# 6_LIN.net
KiCad netlist of a schematic drawn in EAGLE
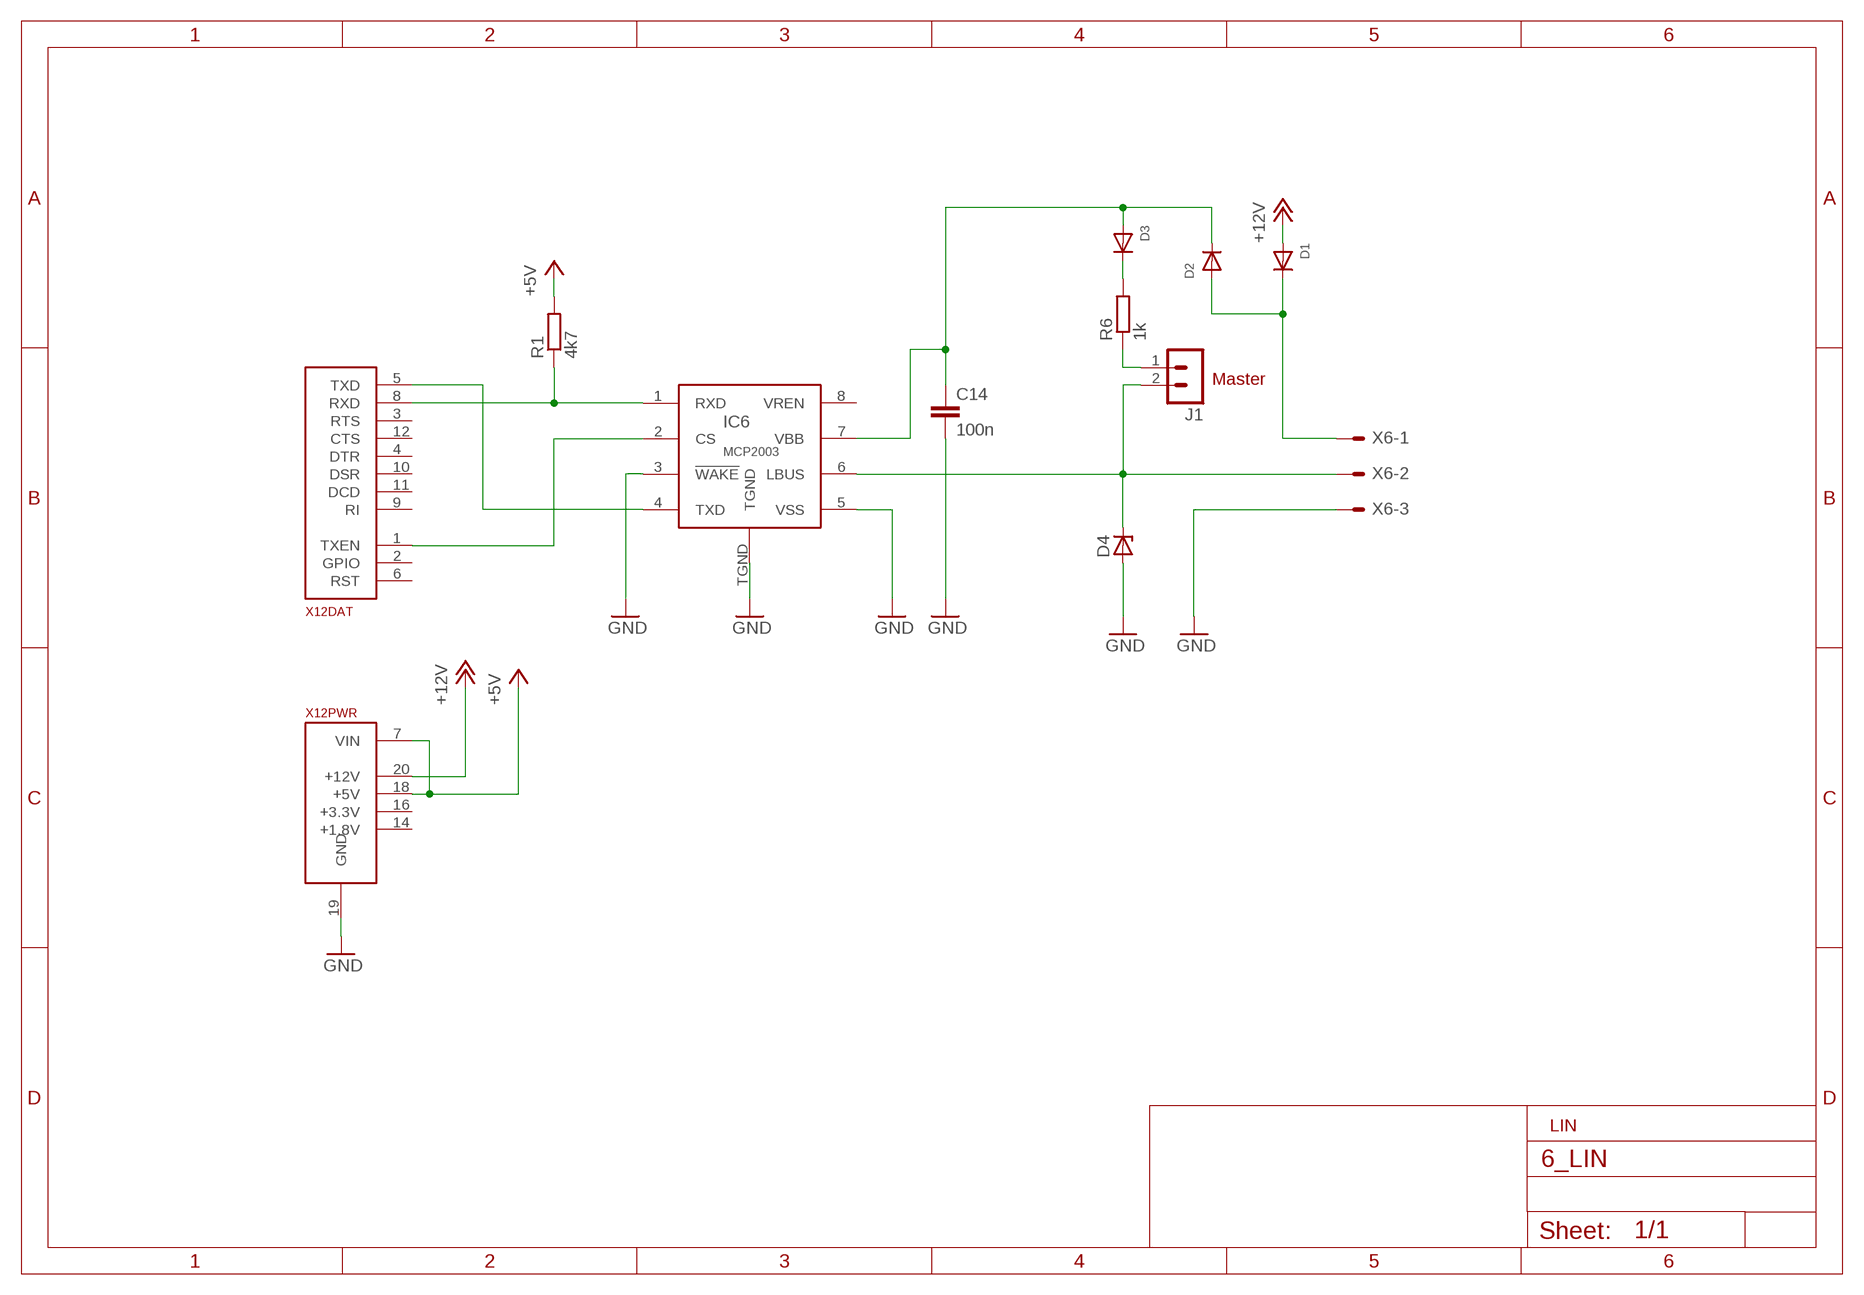
[diagram p0: schematic, sheet 1]

(export (version "E")
  (design (tool "Eeschema 10.0.6"))
  (components
    (comp (ref "C14")
      (value "100n")
      (footprint "eagle-import:C0805")
      (libsource (lib "eagle-import") (part "C-EUC0805"))
    )
    (comp (ref "D1")
      (value "DIODESOD-123")
      (footprint "eagle-import:SOD-123")
      (libsource (lib "eagle-import") (part "DIODESOD-123"))
    )
    (comp (ref "D2")
      (value "DIODESOD-123")
      (footprint "eagle-import:SOD-123")
      (libsource (lib "eagle-import") (part "DIODESOD-123"))
    )
    (comp (ref "D3")
      (value "DIODESOD-123")
      (footprint "eagle-import:SOD-123")
      (libsource (lib "eagle-import") (part "DIODESOD-123"))
    )
    (comp (ref "D4")
      (value "ZENER-DIODESOT23")
      (footprint "eagle-import:SOT23")
      (libsource (lib "eagle-import") (part "ZENER-DIODESOT23"))
    )
    (comp (ref "IC6")
      (value "MCP2003")
      (footprint "eagle-import:SOIC8T")
      (libsource (lib "eagle-import") (part "MCP2003"))
    )
    (comp (ref "J1")
      (value "MA02-1W")
      (footprint "eagle-import:MA02-W")
      (libsource (lib "eagle-import") (part "MA02-1W"))
    )
    (comp (ref "R1")
      (value "4k7")
      (footprint "eagle-import:R0805")
      (libsource (lib "eagle-import") (part "R-EU_R0805"))
    )
    (comp (ref "R6")
      (value "1k")
      (footprint "eagle-import:R0805")
      (libsource (lib "eagle-import") (part "R-EU_R0805"))
    )
    (comp (ref "X6")
      (value "AKL18X-03W")
      (footprint "eagle-import:AKL182-03")
      (libsource (lib "eagle-import") (part "AKL18X-03W"))
    )
    (comp (ref "X12")
      (value "ALLSERIALD")
      (footprint "eagle-import:DAUGHTER-THT")
      (libsource (lib "eagle-import") (part "ALLSERIALD"))
    )
  )
  (nets
    (net (code "1") (name "+5V") (class "Default")
      (node (ref "R1") (pin "2") (pinfunction "2_2") (pintype "passive"))
      (node (ref "X12") (pin "18") (pinfunction "+5V_18") (pintype "bidirectional"))
      (node (ref "X12") (pin "7") (pinfunction "VIN_7") (pintype "bidirectional"))
    )
    (net (code "2") (name "+12V") (class "Default")
      (node (ref "D1") (pin "A") (pinfunction "A_A") (pintype "passive"))
      (node (ref "X12") (pin "20") (pinfunction "+12V_20") (pintype "bidirectional"))
    )
    (net (code "3") (name "GND") (class "Default")
      (node (ref "C14") (pin "2") (pinfunction "2_2") (pintype "passive"))
      (node (ref "D4") (pin "1") (pinfunction "A_1") (pintype "passive"))
      (node (ref "IC6") (pin "3") (pinfunction "~{WAKE}_3") (pintype "input"))
      (node (ref "IC6") (pin "5") (pinfunction "VSS_5") (pintype "power_in"))
      (node (ref "IC6") (pin "TGND") (pinfunction "TGND_TGND") (pintype "power_in"))
      (node (ref "X12") (pin "19") (pinfunction "GND_19") (pintype "bidirectional"))
      (node (ref "X6") (pin "P$3") (pinfunction "S_P$3") (pintype "passive"))
    )
    (net (code "4") (name "Net-(D3-PadC)") (class "Default")
      (node (ref "D3") (pin "C") (pinfunction "C_C") (pintype "passive"))
      (node (ref "R6") (pin "2") (pinfunction "2_2") (pintype "passive"))
    )
    (net (code "5") (name "Net-(D4-C)") (class "Default")
      (node (ref "D4") (pin "3") (pinfunction "C_3") (pintype "passive"))
      (node (ref "IC6") (pin "6") (pinfunction "LBUS_6") (pintype "bidirectional"))
      (node (ref "J1") (pin "2") (pinfunction "2_2") (pintype "passive"))
      (node (ref "X6") (pin "P$2") (pinfunction "S_P$2") (pintype "passive"))
    )
    (net (code "6") (name "Net-(IC6-CS)") (class "Default")
      (node (ref "IC6") (pin "2") (pinfunction "CS_2") (pintype "input"))
      (node (ref "X12") (pin "1") (pinfunction "TXEN_1") (pintype "bidirectional"))
    )
    (net (code "7") (name "Net-(IC6-RXD)") (class "Default")
      (node (ref "IC6") (pin "1") (pinfunction "RXD_1") (pintype "input"))
      (node (ref "R1") (pin "1") (pinfunction "1_1") (pintype "passive"))
      (node (ref "X12") (pin "8") (pinfunction "RXD_8") (pintype "bidirectional"))
    )
    (net (code "8") (name "Net-(IC6-TXD)") (class "Default")
      (node (ref "IC6") (pin "4") (pinfunction "TXD_4") (pintype "output"))
      (node (ref "X12") (pin "5") (pinfunction "TXD_5") (pintype "bidirectional"))
    )
    (net (code "9") (name "Net-(IC6-VBB)") (class "Default")
      (node (ref "C14") (pin "1") (pinfunction "1_1") (pintype "passive"))
      (node (ref "D2") (pin "C") (pinfunction "C_C") (pintype "passive"))
      (node (ref "D3") (pin "A") (pinfunction "A_A") (pintype "passive"))
      (node (ref "IC6") (pin "7") (pinfunction "VBB_7") (pintype "power_in"))
    )
    (net (code "10") (name "Net-(J1-Pad1)") (class "Default")
      (node (ref "J1") (pin "1") (pinfunction "1_1") (pintype "passive"))
      (node (ref "R6") (pin "1") (pinfunction "1_1") (pintype "passive"))
    )
    (net (code "11") (name "Net-(X6A-S)") (class "Default")
      (node (ref "D1") (pin "C") (pinfunction "C_C") (pintype "passive"))
      (node (ref "D2") (pin "A") (pinfunction "A_A") (pintype "passive"))
      (node (ref "X6") (pin "P$1") (pinfunction "S_P$1") (pintype "passive"))
    )
    (net (code "12") (name "unconnected-(IC6-VREN-Pad8)") (class "Default")
      (node (ref "IC6") (pin "8") (pinfunction "VREN_8") (pintype "output"))
    )
    (net (code "13") (name "unconnected-(X12A-CTS-Pad12)") (class "Default")
      (node (ref "X12") (pin "12") (pinfunction "CTS_12") (pintype "bidirectional"))
    )
    (net (code "14") (name "unconnected-(X12A-DCD-Pad11)") (class "Default")
      (node (ref "X12") (pin "11") (pinfunction "DCD_11") (pintype "bidirectional"))
    )
    (net (code "15") (name "unconnected-(X12A-DSR-Pad10)") (class "Default")
      (node (ref "X12") (pin "10") (pinfunction "DSR_10") (pintype "bidirectional"))
    )
    (net (code "16") (name "unconnected-(X12A-DTR-Pad4)") (class "Default")
      (node (ref "X12") (pin "4") (pinfunction "DTR_4") (pintype "bidirectional"))
    )
    (net (code "17") (name "unconnected-(X12A-GPIO-Pad2)") (class "Default")
      (node (ref "X12") (pin "2") (pinfunction "GPIO_2") (pintype "bidirectional"))
    )
    (net (code "18") (name "unconnected-(X12A-RI-Pad9)") (class "Default")
      (node (ref "X12") (pin "9") (pinfunction "RI_9") (pintype "bidirectional"))
    )
    (net (code "19") (name "unconnected-(X12A-RST-Pad6)") (class "Default")
      (node (ref "X12") (pin "6") (pinfunction "RST_6") (pintype "bidirectional"))
    )
    (net (code "20") (name "unconnected-(X12A-RTS-Pad3)") (class "Default")
      (node (ref "X12") (pin "3") (pinfunction "RTS_3") (pintype "bidirectional"))
    )
    (net (code "21") (name "unconnected-(X12B-+1.8V-Pad14)") (class "Default")
      (node (ref "X12") (pin "14") (pinfunction "+1.8V_14") (pintype "bidirectional"))
    )
    (net (code "22") (name "unconnected-(X12B-+3.3V-Pad16)") (class "Default")
      (node (ref "X12") (pin "16") (pinfunction "+3.3V_16") (pintype "bidirectional"))
    )
  )
)
